# MARS_FTDI.net
KiCad netlist of a schematic drawn in Altium Designer
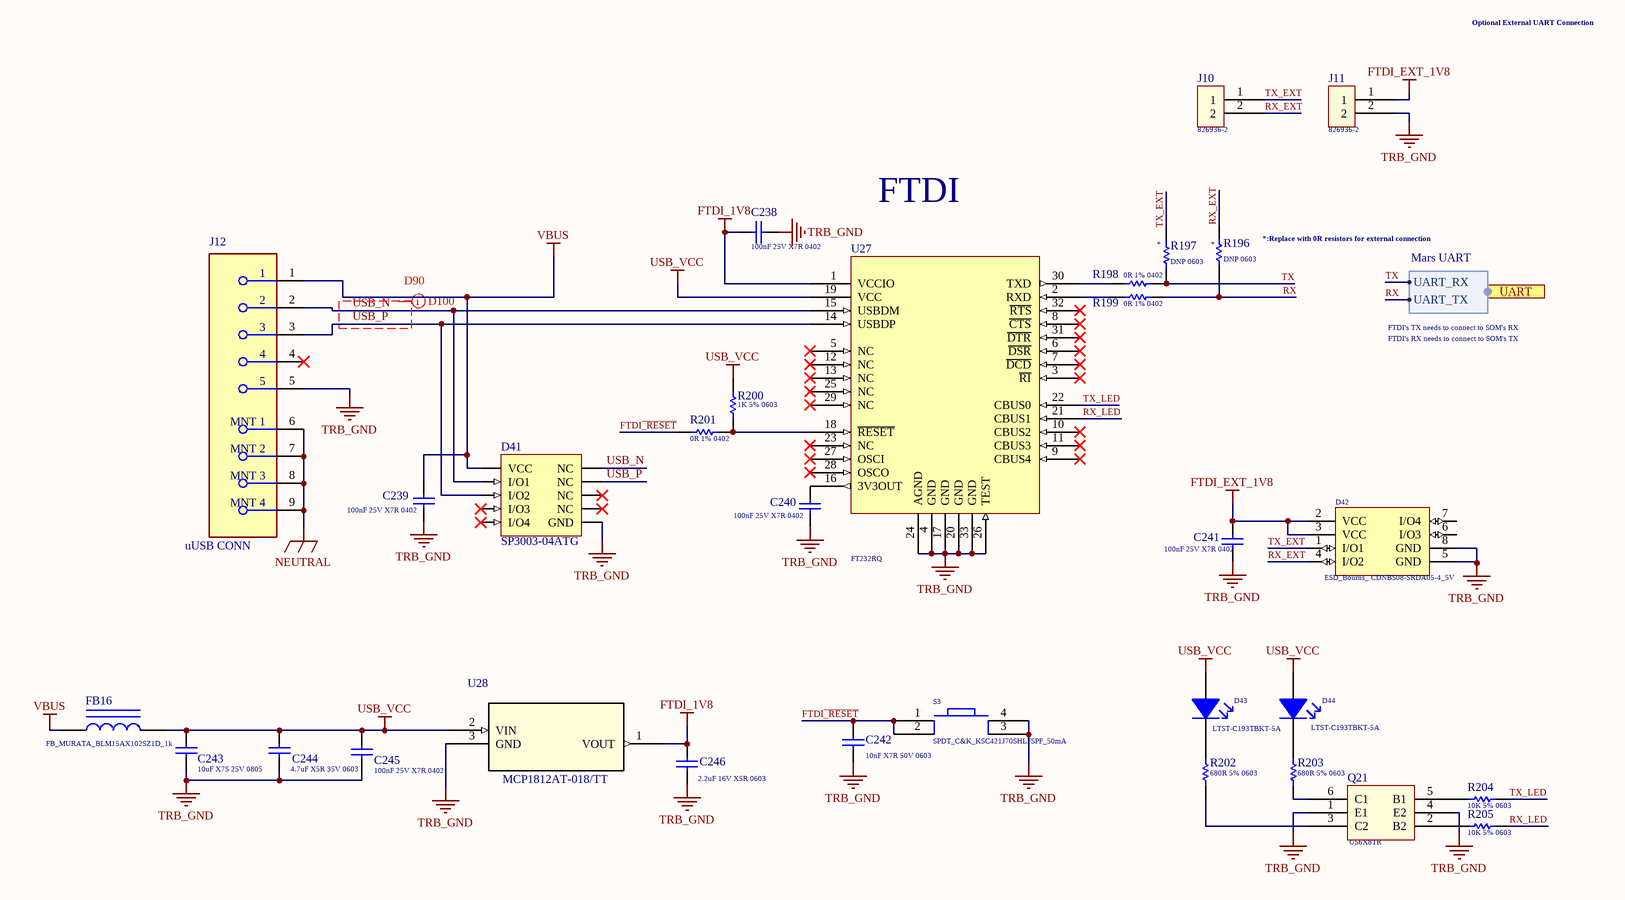
[diagram p0: MARS_FTDI.SchDoc]

(export (version "E")
  (design (tool "Eeschema 10.0.6"))
  (components
    (comp (ref "C238")
      (value "Cap_Taiyo_Yuden_TMK105B7104KV-FR_100nF")
      (footprint "Cap_Taiyo_Yuden_TMK105B7104KV-FR_100nF")
      (description "CAP CER 100nF 25V X7R 0402")
      (fields (field (name "CAPACITANCE") "100nF 25V X7R 0402"))
      (libsource (lib "Cap_Taiyo_Yuden_TMK105B7104KV-FR_100nF") (part "Cap_Taiyo_Yuden_TMK105B7104KV-FR_100nF"))
    )
    (comp (ref "C239")
      (value "Cap_Taiyo_Yuden_TMK105B7104KV-FR_100nF")
      (footprint "Cap_Taiyo_Yuden_TMK105B7104KV-FR_100nF")
      (description "CAP CER 100nF 25V X7R 0402")
      (fields (field (name "CAPACITANCE") "100nF 25V X7R 0402"))
      (libsource (lib "Cap_Taiyo_Yuden_TMK105B7104KV-FR_100nF") (part "Cap_Taiyo_Yuden_TMK105B7104KV-FR_100nF"))
    )
    (comp (ref "C240")
      (value "Cap_Taiyo_Yuden_TMK105B7104KV-FR_100nF")
      (footprint "Cap_Taiyo_Yuden_TMK105B7104KV-FR_100nF")
      (description "CAP CER 100nF 25V X7R 0402")
      (fields (field (name "CAPACITANCE") "100nF 25V X7R 0402"))
      (libsource (lib "Cap_Taiyo_Yuden_TMK105B7104KV-FR_100nF") (part "Cap_Taiyo_Yuden_TMK105B7104KV-FR_100nF"))
    )
    (comp (ref "C241")
      (value "Cap_Taiyo_Yuden_TMK105B7104KV-FR_100nF")
      (footprint "Cap_Taiyo_Yuden_TMK105B7104KV-FR_100nF")
      (description "CAP CER 100nF 25V X7R 0402")
      (fields (field (name "CAPACITANCE") "100nF 25V X7R 0402"))
      (libsource (lib "Cap_Taiyo_Yuden_TMK105B7104KV-FR_100nF") (part "Cap_Taiyo_Yuden_TMK105B7104KV-FR_100nF"))
    )
    (comp (ref "C242")
      (value "Cap_Kemet_C0603C103J5RACTU_eec")
      (footprint "Kemet_C0603_0")
      (description "CAP CER 10nF 50V X7R 0603")
      (fields
        (field (name "PART NUMBER") "C0603C103J5RACTU")
        (field (name "MANUFACTURER") "Kemet")
        (field (name "CAPACITANCE") "10nF X7R 50V 0603")
      )
      (libsource (lib "Cap_Kemet_C0603C103J5RACTU_10nF") (part "Cap_Kemet_C0603C103J5RACTU_eec"))
    )
    (comp (ref "C243")
      (value "Cap_Murata_ GRM21BC71E106ME11L_10uF")
      (footprint "Cap_Murata_ GRM21BC71E106ME11L_10uF")
      (description "CAP CER 10uF 25V X7R 0805")
      (fields (field (name "CAPACITANCE") "10uF X7S 25V 0805"))
      (libsource (lib "Cap_Murata_ GRM21BC71E106ME11L_10uF") (part "Cap_Murata_ GRM21BC71E106ME11L_10uF"))
    )
    (comp (ref "C244")
      (value "Cap_Murata_ZRB18AR6YA475ME05L_4.7uF")
      (footprint "Cap_Murata_ZRB18AR6YA475ME05L_4.7uF")
      (description "CAP CER 4.7uF 35V X5R 0603")
      (fields (field (name "CAPACITANCE") "4.7uF X5R 35V 0603"))
      (libsource (lib "Cap_Murata_ZRB18AR6YA475ME05L_4.7uF") (part "Cap_Murata_ZRB18AR6YA475ME05L_4.7uF"))
    )
    (comp (ref "C245")
      (value "Cap_Taiyo_Yuden_TMK105B7104KV-FR_100nF")
      (footprint "Cap_Taiyo_Yuden_TMK105B7104KV-FR_100nF")
      (description "CAP CER 100nF 25V X7R 0402")
      (fields (field (name "CAPACITANCE") "100nF 25V X7R 0402"))
      (libsource (lib "Cap_Taiyo_Yuden_TMK105B7104KV-FR_100nF") (part "Cap_Taiyo_Yuden_TMK105B7104KV-FR_100nF"))
    )
    (comp (ref "C246")
      (value "Cap_Taiyo_Yuden_2.2uF")
      (footprint "CAPC0603(1608)100_L")
      (description "CAP 2.2uF 16V ±10% 0603 (1608 Metric) Thickness 1mm SMD")
      (fields (field (name "TOLERANCE") "Â±10%") (field (name "CAPACITANCE") "2.2uF 16V X5R 0603"))
      (libsource (lib "Altium Content Vault") (part "CAP"))
    )
    (comp (ref "D41")
      (value "Diode_SP3003-04ATG_LVDS_ESD")
      (footprint "Diode_SP3003-04ATG_LVDS_ESD")
      (description "ESD Suppressors / TVS Diodes 4 Ch 8kV 0.65pF SPA")
      (fields (field (name "SERIES") "SP3003-04ATG"))
      (libsource (lib "Diode_SP3003-04ATG_LVDS_ESD") (part "Diode_SP3003-04ATG_LVDS_ESD"))
    )
    (comp (ref "D42")
      (value "ESD_Bourns_ CDNBS08-SRDA05-4_5V")
      (footprint "ESD_Bourns_ CDNBS08-SRDA05-4_5V")
      (description "ESD Suppressors / TVS Diodes SO-8 5V 500W Low Capacitance")
      (libsource (lib "ESD_Bourns_ CDNBS08-SRDA05-4_5V") (part "ESD_Bourns_ CDNBS08-SRDA05-4_5V"))
    )
    (comp (ref "D43")
      (value "Led_Lite-On_LTST-C193TBKT-5A_Blue")
      (footprint "Led_Lite-On_LTST-C193TBKT-5A_Blue")
      (description "Standard LEDs - SMD Blue 470nm 28mcd 20mA")
      (fields (field (name "SERIES") "LTST-C193TBKT-5A"))
      (libsource (lib "Led_Lite-On_LTST-C193TBKT-5A_Blue") (part "Led_Lite-On_LTST-C193TBKT-5A_Blue"))
    )
    (comp (ref "D44")
      (value "Led_Lite-On_LTST-C193TBKT-5A_Blue")
      (footprint "Led_Lite-On_LTST-C193TBKT-5A_Blue")
      (description "Standard LEDs - SMD Blue 470nm 28mcd 20mA")
      (fields (field (name "SERIES") "LTST-C193TBKT-5A"))
      (libsource (lib "Led_Lite-On_LTST-C193TBKT-5A_Blue") (part "Led_Lite-On_LTST-C193TBKT-5A_Blue"))
    )
    (comp (ref "FB16")
      (value "FB_MURATA_BLM15AX102SZ1D_1k")
      (footprint "FB_MURATA_BLM15AX102SZ1D_1k")
      (description "FB SMD 1000 OHM 25% 3/4W 0402")
      (libsource (lib "FB_MURATA_BLM15AX102SZ1D_1k") (part "FB_MURATA_BLM15AX102SZ1D_1k"))
    )
    (comp (ref "J10")
      (value "Header_TE_Connectivity_826936-2_2POS_5A")
      (footprint "Header_TE_Connectivity_826936-2_2POS_5A")
      (description "Headers & Wire Housings 2P SINGLE ROW 5A")
      (fields (field (name "SERIES") "826936-2"))
      (libsource (lib "Header_TE_Connectivity_826936-2_2POS_5A") (part "Header_TE_Connectivity_826936-2_2POS_5A"))
    )
    (comp (ref "J11")
      (value "Header_TE_Connectivity_826936-2_2POS_5A")
      (footprint "Header_TE_Connectivity_826936-2_2POS_5A")
      (description "Headers & Wire Housings 2P SINGLE ROW 5A")
      (fields (field (name "SERIES") "826936-2"))
      (libsource (lib "Header_TE_Connectivity_826936-2_2POS_5A") (part "Header_TE_Connectivity_826936-2_2POS_5A"))
    )
    (comp (ref "J12")
      (value "uUSB CONN")
      (footprint "Wurth_Electronics_629105150521_MFG")
      (description "USB Connectors WR-COM USB Micro SMT Type B Horiztl")
      (libsource (lib "Conn_Wurth_Electronics_629105150521_eec") (part "629105150521"))
    )
    (comp (ref "Q21")
      (value "BJT_ROHM_US6X8TR_1A_NPN")
      (footprint "BJT_ROHM_US6X8TR_1A_NPN")
      (description "Bipolar Transistors - BJT NPN+NPN 30VCEO 1A SOT-363T")
      (fields (field (name "SERIES") "US6X8TR"))
      (libsource (lib "BJT_ROHM_US6X8TR_1A_NPN") (part "BJT_ROHM_US6X8TR_1A_NPN"))
    )
    (comp (ref "R196")
      (value "RES_DNP_0603")
      (footprint "RES_DNP_0603")
      (description "0603 Do not place resistor")
      (fields (field (name "RESISTANCE") "DNP 0603"))
      (libsource (lib "RES_DNP_0603") (part "RES_DNP_0603"))
    )
    (comp (ref "R197")
      (value "RES_DNP_0603")
      (footprint "RES_DNP_0603")
      (description "0603 Do not place resistor")
      (fields (field (name "RESISTANCE") "DNP 0603"))
      (libsource (lib "RES_DNP_0603") (part "RES_DNP_0603"))
    )
    (comp (ref "R198")
      (value "Res_Vishay_CRCW04020000Z0EDC_0_Ohm")
      (footprint "Res_Vishay_CRCW04020000Z0EDC_0_Ohm")
      (description "0R 0.062W 1% 0402 (1005 Metric)  SMD")
      (fields (field (name "RESISTANCE") "0R 1% 0402"))
      (libsource (lib "Res_Vishay_CRCW04020000Z0EDC_0_Ohm") (part "Res_Vishay_CRCW04020000Z0EDC_0_Ohm"))
    )
    (comp (ref "R199")
      (value "Res_Vishay_CRCW04020000Z0EDC_0_Ohm")
      (footprint "Res_Vishay_CRCW04020000Z0EDC_0_Ohm")
      (description "0R 0.062W 1% 0402 (1005 Metric)  SMD")
      (fields (field (name "RESISTANCE") "0R 1% 0402"))
      (libsource (lib "Res_Vishay_CRCW04020000Z0EDC_0_Ohm") (part "Res_Vishay_CRCW04020000Z0EDC_0_Ohm"))
    )
    (comp (ref "R200")
      (value "1K 5% 0603")
      (footprint "RESC0603(1608)_L")
      (description "1K 0.1W 5% 0603 (1608 Metric)  SMD")
      (fields (field (name "TOLERANCE") "5 %") (field (name "POWER") "0.1 W"))
      (libsource (lib "Altium Content Vault") (part "RES"))
    )
    (comp (ref "R201")
      (value "Res_Vishay_CRCW04020000Z0EDC_0_Ohm")
      (footprint "Res_Vishay_CRCW04020000Z0EDC_0_Ohm")
      (description "0R 0.062W 1% 0402 (1005 Metric)  SMD")
      (fields (field (name "RESISTANCE") "0R 1% 0402"))
      (libsource (lib "Res_Vishay_CRCW04020000Z0EDC_0_Ohm") (part "Res_Vishay_CRCW04020000Z0EDC_0_Ohm"))
    )
    (comp (ref "R202")
      (value "680R 5% 0603")
      (footprint "RESC0603(1608)_L")
      (description "680R 0.1W 5% 0603 (1608 Metric)  SMD")
      (fields (field (name "TOLERANCE") "5 %") (field (name "POWER") "0.1 W"))
      (libsource (lib "Altium Content Vault") (part "RES"))
    )
    (comp (ref "R203")
      (value "680R 5% 0603")
      (footprint "RESC0603(1608)_L")
      (description "680R 0.1W 5% 0603 (1608 Metric)  SMD")
      (fields (field (name "TOLERANCE") "5 %") (field (name "POWER") "0.1 W"))
      (libsource (lib "Altium Content Vault") (part "RES"))
    )
    (comp (ref "R204")
      (value "10K 5% 0603")
      (footprint "RESC0603(1608)_L")
      (description "10K 0.1W 5% 0603 (1608 Metric)  SMD")
      (fields (field (name "TOLERANCE") "5 %") (field (name "POWER") "0.1 W"))
      (libsource (lib "Altium Content Vault") (part "RES"))
    )
    (comp (ref "R205")
      (value "10K 5% 0603")
      (footprint "RESC0603(1608)_L")
      (description "10K 0.1W 5% 0603 (1608 Metric)  SMD")
      (fields (field (name "TOLERANCE") "5 %") (field (name "POWER") "0.1 W"))
      (libsource (lib "Altium Content Vault") (part "RES"))
    )
    (comp (ref "S3")
      (value "SPDT_C&K_KSC421J70SHLFSPF_50mA")
      (footprint "SPDT_C&K_KSC421J70SHLFSPF_50mA")
      (description "Tactile Switches Tact 6.2 x 6.2, 5.1 mm H, 1.7N, J leads, Potting Friendly, IP67")
      (libsource (lib "SPDT_C&K_KSC421J70SHLFSPF_50mA") (part "SPDT_C&K_KSC421J70SHLFSPF_50mA"))
    )
    (comp (ref "U27")
      (value "IC_FTDI_FT232RQ-REEL")
      (footprint "IC_FTDI_FT232RQ-REEL")
      (description "USB Interface IC USB to Serial UART Enhanced IC QFN-32")
      (fields (field (name "SERIES") "FT232RQ"))
      (libsource (lib "IC_FTDI_FT232RQ-REEL") (part "IC_FTDI_FT232RQ-REEL"))
    )
    (comp (ref "U28")
      (value "MCP1812AT-018/TT")
      (footprint "SOT23_TT_MCH")
      (description "LDO Voltage Regulators 1.8V 3-Lead SOT-23 300mA Ultra Low Iq LDO with Auto-Discharge")
      (fields (field (name "COPYRIGHT") "Copyright (C) 2018 Accelerated Designs. All rights reserved"))
      (libsource (lib "LDO_Microchip_MCP1812AT-018TT_1V8") (part "MCP1812AT-018/TT"))
    )
  )
  (nets
    (net (code "3") (name "/FTDI~{_RESET}") (class "Default")
      (node (ref "C242") (pin "1") (pinfunction "1_1") (pintype "passive"))
      (node (ref "R201") (pin "2") (pinfunction "2_2") (pintype "passive"))
      (node (ref "S3") (pin "1") (pintype "passive"))
      (node (ref "S3") (pin "2") (pintype "passive"))
    )
    (net (code "4") (name "/RX") (class "Default")
      (node (ref "R196") (pin "2") (pinfunction "2_2") (pintype "passive"))
      (node (ref "R199") (pin "2") (pinfunction "2_2") (pintype "passive"))
    )
    (net (code "5") (name "/RX_EXT") (class "Default")
      (node (ref "D42") (pin "4") (pinfunction "I/O2_4") (pintype "bidirectional"))
      (node (ref "J10") (pin "2") (pinfunction "2_2") (pintype "passive"))
      (node (ref "R196") (pin "1") (pinfunction "1_1") (pintype "passive"))
    )
    (net (code "6") (name "/RX_LED") (class "Default")
      (node (ref "R205") (pin "1") (pinfunction "1_1") (pintype "passive"))
      (node (ref "U27") (pin "21") (pinfunction "CBUS1_21") (pintype "input"))
    )
    (net (code "7") (name "/TX") (class "Default")
      (node (ref "R197") (pin "2") (pinfunction "2_2") (pintype "passive"))
      (node (ref "R198") (pin "2") (pinfunction "2_2") (pintype "passive"))
    )
    (net (code "8") (name "/TX_EXT") (class "Default")
      (node (ref "D42") (pin "1") (pinfunction "I/O1_1") (pintype "bidirectional"))
      (node (ref "J10") (pin "1") (pinfunction "1_1") (pintype "passive"))
      (node (ref "R197") (pin "1") (pinfunction "1_1") (pintype "passive"))
    )
    (net (code "9") (name "/TX_LED") (class "Default")
      (node (ref "R204") (pin "2") (pinfunction "2_2") (pintype "passive"))
      (node (ref "U27") (pin "22") (pinfunction "CBUS0_22") (pintype "input"))
    )
    (net (code "10") (name "/USB_N") (class "Default")
      (node (ref "D41") (pin "1") (pinfunction "I/O1_1") (pintype "input"))
      (node (ref "D41") (pin "10") (pinfunction "NC_10") (pintype "tri_state"))
      (node (ref "J12") (pin "2") (pinfunction "2_2") (pintype "passive"))
      (node (ref "U27") (pin "15") (pinfunction "USBDM_15") (pintype "input"))
    )
    (net (code "11") (name "/USB_P") (class "Default")
      (node (ref "D41") (pin "2") (pinfunction "I/O2_2") (pintype "input"))
      (node (ref "D41") (pin "9") (pinfunction "NC_9") (pintype "tri_state"))
      (node (ref "J12") (pin "3") (pinfunction "3_3") (pintype "passive"))
      (node (ref "U27") (pin "14") (pinfunction "USBDP_14") (pintype "input"))
    )
    (net (code "13") (name "FTDI_1V8") (class "Default")
      (node (ref "C238") (pin "2") (pinfunction "2_2") (pintype "passive"))
      (node (ref "C246") (pin "2") (pinfunction "2_2") (pintype "passive"))
      (node (ref "U27") (pin "1") (pinfunction "VCCIO_1") (pintype "power_in"))
      (node (ref "U28") (pin "1") (pinfunction "VOUT_1") (pintype "output"))
    )
    (net (code "14") (name "FTDI_EXT_1V8") (class "Default")
      (node (ref "C241") (pin "2") (pinfunction "2_2") (pintype "passive"))
      (node (ref "D42") (pin "2") (pinfunction "VCC_2") (pintype "power_in"))
      (node (ref "D42") (pin "3") (pinfunction "VCC_3") (pintype "power_in"))
      (node (ref "J11") (pin "1") (pinfunction "1_1") (pintype "passive"))
    )
    (net (code "15") (name "NEUTRAL") (class "Default")
      (node (ref "J12") (pin "6") (pinfunction "MNT_1_6") (pintype "passive"))
      (node (ref "J12") (pin "7") (pinfunction "MNT_2_7") (pintype "passive"))
      (node (ref "J12") (pin "8") (pinfunction "MNT_3_8") (pintype "passive"))
      (node (ref "J12") (pin "9") (pinfunction "MNT_4_9") (pintype "passive"))
    )
    (net (code "16") (name "Net-(D43-K)") (class "Default")
      (node (ref "D43") (pin "1") (pinfunction "K_1") (pintype "passive"))
      (node (ref "R202") (pin "2") (pinfunction "2_2") (pintype "passive"))
    )
    (net (code "17") (name "Net-(D44-K)") (class "Default")
      (node (ref "D44") (pin "1") (pinfunction "K_1") (pintype "passive"))
      (node (ref "R203") (pin "2") (pinfunction "2_2") (pintype "passive"))
    )
    (net (code "18") (name "Net-(Q21-B1)") (class "Default")
      (node (ref "Q21") (pin "5") (pinfunction "B1_5") (pintype "passive"))
      (node (ref "R204") (pin "1") (pinfunction "1_1") (pintype "passive"))
    )
    (net (code "19") (name "Net-(Q21-B2)") (class "Default")
      (node (ref "Q21") (pin "2") (pinfunction "B2_2") (pintype "passive"))
      (node (ref "R205") (pin "2") (pinfunction "2_2") (pintype "passive"))
    )
    (net (code "20") (name "Net-(Q21-C1)") (class "Default")
      (node (ref "Q21") (pin "6") (pinfunction "C1_6") (pintype "passive"))
      (node (ref "R203") (pin "1") (pinfunction "1_1") (pintype "passive"))
    )
    (net (code "21") (name "Net-(Q21-C2)") (class "Default")
      (node (ref "Q21") (pin "3") (pinfunction "C2_3") (pintype "passive"))
      (node (ref "R202") (pin "1") (pinfunction "1_1") (pintype "passive"))
    )
    (net (code "22") (name "Net-(U27-3V3OUT)") (class "Default")
      (node (ref "C240") (pin "2") (pinfunction "2_2") (pintype "passive"))
      (node (ref "U27") (pin "16") (pinfunction "3V3OUT_16") (pintype "output"))
    )
    (net (code "23") (name "Net-(U27-RXD)") (class "Default")
      (node (ref "R199") (pin "1") (pinfunction "1_1") (pintype "passive"))
      (node (ref "U27") (pin "2") (pinfunction "RXD_2") (pintype "input"))
    )
    (net (code "24") (name "Net-(U27-TXD)") (class "Default")
      (node (ref "R198") (pin "1") (pinfunction "1_1") (pintype "passive"))
      (node (ref "U27") (pin "30") (pinfunction "TXD_30") (pintype "output"))
    )
    (net (code "25") (name "Net-(U27-~{RESET})") (class "Default")
      (node (ref "R200") (pin "1") (pinfunction "1_1") (pintype "passive"))
      (node (ref "R201") (pin "1") (pinfunction "1_1") (pintype "passive"))
      (node (ref "U27") (pin "18") (pinfunction "~{RESET}_18") (pintype "input"))
    )
    (net (code "26") (name "TRB_GND") (class "Default")
      (node (ref "C238") (pin "1") (pinfunction "1_1") (pintype "passive"))
      (node (ref "C239") (pin "1") (pinfunction "1_1") (pintype "passive"))
      (node (ref "C240") (pin "1") (pinfunction "1_1") (pintype "passive"))
      (node (ref "C241") (pin "1") (pinfunction "1_1") (pintype "passive"))
      (node (ref "C242") (pin "2") (pinfunction "2_2") (pintype "passive"))
      (node (ref "C243") (pin "2") (pinfunction "2_2") (pintype "passive"))
      (node (ref "C244") (pin "1") (pinfunction "1_1") (pintype "passive"))
      (node (ref "C245") (pin "1") (pinfunction "1_1") (pintype "passive"))
      (node (ref "C246") (pin "1") (pinfunction "1_1") (pintype "passive"))
      (node (ref "D41") (pin "8") (pinfunction "GND_8") (pintype "power_in"))
      (node (ref "D42") (pin "5") (pinfunction "GND_5") (pintype "power_in"))
      (node (ref "D42") (pin "8") (pinfunction "GND_8") (pintype "power_in"))
      (node (ref "J11") (pin "2") (pinfunction "2_2") (pintype "passive"))
      (node (ref "J12") (pin "5") (pinfunction "5_5") (pintype "passive"))
      (node (ref "Q21") (pin "1") (pinfunction "E1_1") (pintype "passive"))
      (node (ref "Q21") (pin "4") (pinfunction "E2_4") (pintype "passive"))
      (node (ref "S3") (pin "3") (pintype "passive"))
      (node (ref "S3") (pin "4") (pintype "passive"))
      (node (ref "U27") (pin "17") (pinfunction "GND_17") (pintype "power_in"))
      (node (ref "U27") (pin "20") (pinfunction "GND_20") (pintype "power_in"))
      (node (ref "U27") (pin "24") (pinfunction "AGND_24") (pintype "power_in"))
      (node (ref "U27") (pin "26") (pinfunction "TEST_26") (pintype "input"))
      (node (ref "U27") (pin "33") (pinfunction "GND_33") (pintype "power_in"))
      (node (ref "U27") (pin "4") (pinfunction "GND_4") (pintype "power_in"))
      (node (ref "U28") (pin "3") (pinfunction "GND_3") (pintype "passive"))
    )
    (net (code "27") (name "USB_VCC") (class "Default")
      (node (ref "C243") (pin "1") (pinfunction "1_1") (pintype "passive"))
      (node (ref "C244") (pin "2") (pinfunction "2_2") (pintype "passive"))
      (node (ref "C245") (pin "2") (pinfunction "2_2") (pintype "passive"))
      (node (ref "D43") (pin "2") (pinfunction "A_2") (pintype "passive"))
      (node (ref "D44") (pin "2") (pinfunction "A_2") (pintype "passive"))
      (node (ref "FB16") (pin "2") (pinfunction "2_2") (pintype "passive"))
      (node (ref "R200") (pin "2") (pinfunction "2_2") (pintype "passive"))
      (node (ref "U27") (pin "19") (pinfunction "VCC_19") (pintype "power_in"))
      (node (ref "U28") (pin "2") (pinfunction "VIN_2") (pintype "input"))
    )
    (net (code "28") (name "VBUS") (class "Default")
      (node (ref "C239") (pin "2") (pinfunction "2_2") (pintype "passive"))
      (node (ref "D41") (pin "3") (pinfunction "VCC_3") (pintype "passive"))
      (node (ref "FB16") (pin "1") (pinfunction "1_1") (pintype "passive"))
      (node (ref "J12") (pin "1") (pinfunction "1_1") (pintype "passive"))
    )
    (net (code "29") (name "unconnected-(D41-I{slash}O3-Pad4)") (class "Default")
      (node (ref "D41") (pin "4") (pinfunction "I/O3_4") (pintype "input+no_connect"))
    )
    (net (code "30") (name "unconnected-(D41-I{slash}O4-Pad5)") (class "Default")
      (node (ref "D41") (pin "5") (pinfunction "I/O4_5") (pintype "input+no_connect"))
    )
    (net (code "31") (name "unconnected-(D41-NC-Pad6)") (class "Default")
      (node (ref "D41") (pin "6") (pinfunction "NC_6") (pintype "tri_state+no_connect"))
    )
    (net (code "32") (name "unconnected-(D41-NC-Pad7)") (class "Default")
      (node (ref "D41") (pin "7") (pinfunction "NC_7") (pintype "tri_state+no_connect"))
    )
    (net (code "33") (name "unconnected-(D42-I{slash}O3-Pad6)") (class "Default")
      (node (ref "D42") (pin "6") (pinfunction "I/O3_6") (pintype "bidirectional"))
    )
    (net (code "34") (name "unconnected-(D42-I{slash}O4-Pad7)") (class "Default")
      (node (ref "D42") (pin "7") (pinfunction "I/O4_7") (pintype "bidirectional"))
    )
    (net (code "35") (name "unconnected-(J12-Pad4)") (class "Default")
      (node (ref "J12") (pin "4") (pinfunction "4_4") (pintype "passive+no_connect"))
    )
    (net (code "36") (name "unconnected-(U27-CBUS2-Pad10)") (class "Default")
      (node (ref "U27") (pin "10") (pinfunction "CBUS2_10") (pintype "input+no_connect"))
    )
    (net (code "37") (name "unconnected-(U27-CBUS3-Pad11)") (class "Default")
      (node (ref "U27") (pin "11") (pinfunction "CBUS3_11") (pintype "input+no_connect"))
    )
    (net (code "38") (name "unconnected-(U27-CBUS4-Pad9)") (class "Default")
      (node (ref "U27") (pin "9") (pinfunction "CBUS4_9") (pintype "input+no_connect"))
    )
    (net (code "39") (name "unconnected-(U27-NC-Pad5)") (class "Default")
      (node (ref "U27") (pin "5") (pinfunction "NC_5") (pintype "input+no_connect"))
    )
    (net (code "40") (name "unconnected-(U27-NC-Pad12)") (class "Default")
      (node (ref "U27") (pin "12") (pinfunction "NC_12") (pintype "input+no_connect"))
    )
    (net (code "41") (name "unconnected-(U27-NC-Pad13)") (class "Default")
      (node (ref "U27") (pin "13") (pinfunction "NC_13") (pintype "input+no_connect"))
    )
    (net (code "42") (name "unconnected-(U27-NC-Pad23)") (class "Default")
      (node (ref "U27") (pin "23") (pinfunction "NC_23") (pintype "input+no_connect"))
    )
    (net (code "43") (name "unconnected-(U27-NC-Pad25)") (class "Default")
      (node (ref "U27") (pin "25") (pinfunction "NC_25") (pintype "input+no_connect"))
    )
    (net (code "44") (name "unconnected-(U27-NC-Pad29)") (class "Default")
      (node (ref "U27") (pin "29") (pinfunction "NC_29") (pintype "input+no_connect"))
    )
    (net (code "45") (name "unconnected-(U27-OSCI-Pad27)") (class "Default")
      (node (ref "U27") (pin "27") (pinfunction "OSCI_27") (pintype "input+no_connect"))
    )
    (net (code "46") (name "unconnected-(U27-OSCO-Pad28)") (class "Default")
      (node (ref "U27") (pin "28") (pinfunction "OSCO_28") (pintype "input+no_connect"))
    )
    (net (code "47") (name "unconnected-(U27-~{CTS}-Pad8)") (class "Default")
      (node (ref "U27") (pin "8") (pinfunction "~{CTS}_8") (pintype "input+no_connect"))
    )
    (net (code "48") (name "unconnected-(U27-~{DCD}-Pad7)") (class "Default")
      (node (ref "U27") (pin "7") (pinfunction "~{DCD}_7") (pintype "input+no_connect"))
    )
    (net (code "49") (name "unconnected-(U27-~{DSR}-Pad6)") (class "Default")
      (node (ref "U27") (pin "6") (pinfunction "~{DSR}_6") (pintype "input+no_connect"))
    )
    (net (code "50") (name "unconnected-(U27-~{DTR}-Pad31)") (class "Default")
      (node (ref "U27") (pin "31") (pinfunction "~{DTR}_31") (pintype "input+no_connect"))
    )
    (net (code "51") (name "unconnected-(U27-~{RI}-Pad3)") (class "Default")
      (node (ref "U27") (pin "3") (pinfunction "~{RI}_3") (pintype "input+no_connect"))
    )
    (net (code "52") (name "unconnected-(U27-~{RTS}-Pad32)") (class "Default")
      (node (ref "U27") (pin "32") (pinfunction "~{RTS}_32") (pintype "input+no_connect"))
    )
  )
)
